# board.net
KiCad netlist of a schematic drawn in EAGLE
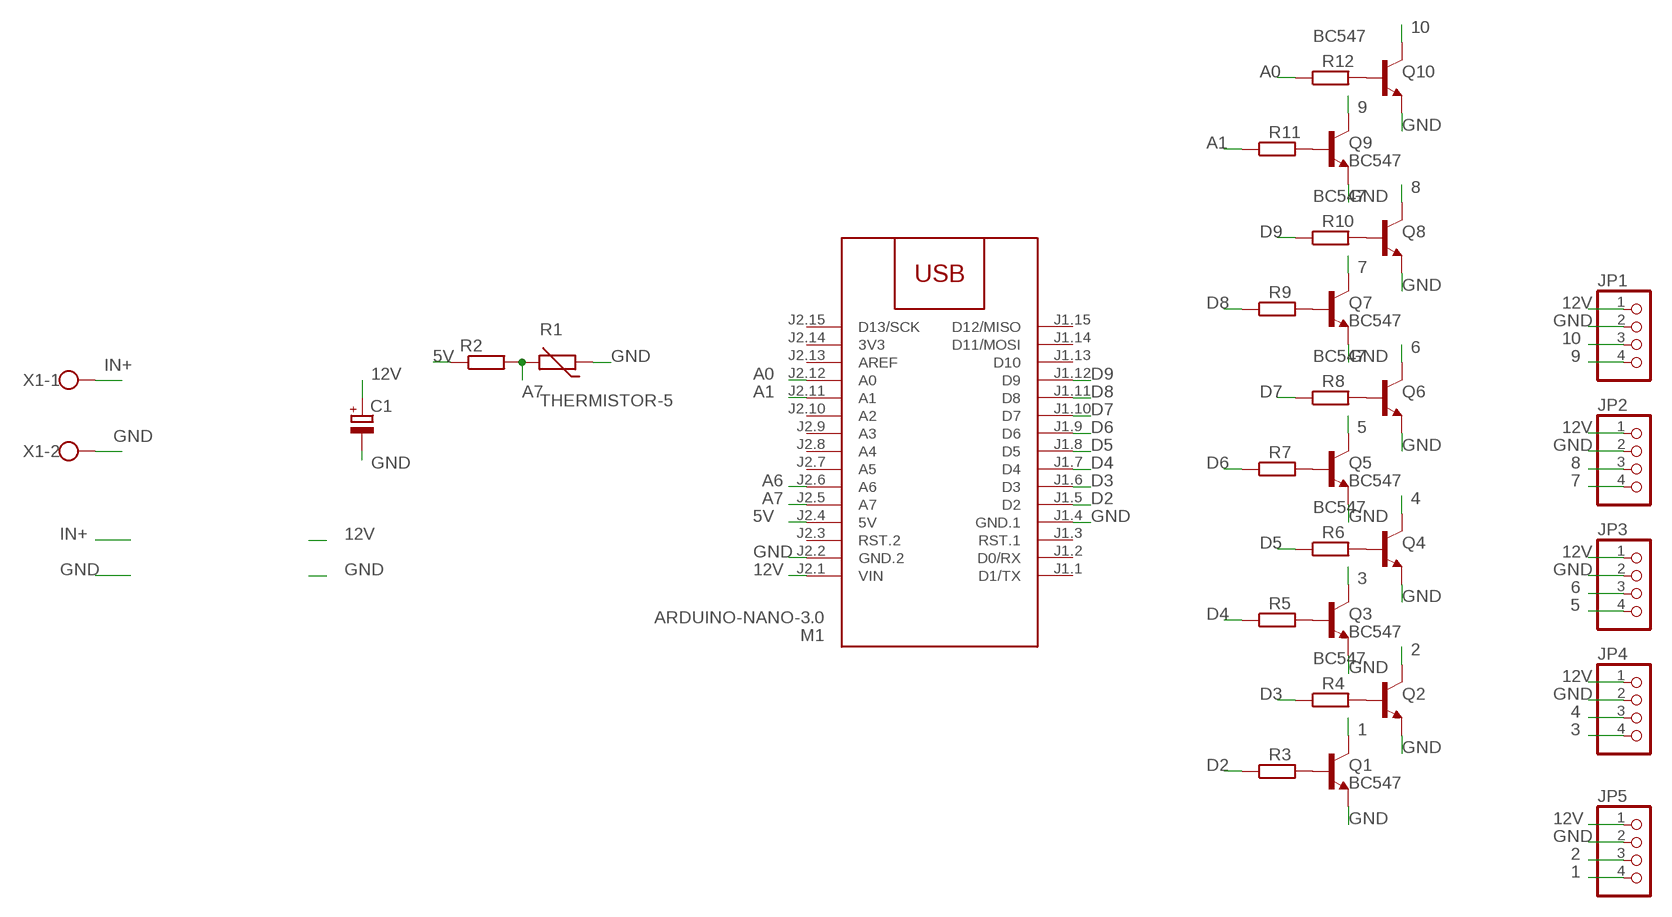
[diagram p0: schematic, sheet 1]

(export (version "E")
  (design (tool "Eeschema 10.0.6"))
  (components
    (comp (ref "C1")
      (value "CPOL-EUB45181A")
      (footprint "eagle-import:B45181A")
      (libsource (lib "eagle-import") (part "CPOL-EUB45181A"))
    )
    (comp (ref "JP1")
      (value "PINHD-1X4")
      (footprint "eagle-import:1X04")
      (libsource (lib "eagle-import") (part "PINHD-1X4"))
    )
    (comp (ref "JP2")
      (value "PINHD-1X4")
      (footprint "eagle-import:1X04")
      (libsource (lib "eagle-import") (part "PINHD-1X4"))
    )
    (comp (ref "JP3")
      (value "PINHD-1X4")
      (footprint "eagle-import:1X04")
      (libsource (lib "eagle-import") (part "PINHD-1X4"))
    )
    (comp (ref "JP4")
      (value "PINHD-1X4")
      (footprint "eagle-import:1X04")
      (libsource (lib "eagle-import") (part "PINHD-1X4"))
    )
    (comp (ref "JP5")
      (value "PINHD-1X4")
      (footprint "eagle-import:1X04")
      (libsource (lib "eagle-import") (part "PINHD-1X4"))
    )
    (comp (ref "M1")
      (value "ARDUINO-NANO-3.0")
      (footprint "eagle-import:ARDUINO-NANO-3.0")
      (libsource (lib "eagle-import") (part "ARDUINO-NANO-3.0"))
    )
    (comp (ref "Q1")
      (value "BC547")
      (footprint "eagle-import:TO92")
      (libsource (lib "eagle-import") (part "BC547"))
    )
    (comp (ref "Q2")
      (value "BC547")
      (footprint "eagle-import:TO92")
      (libsource (lib "eagle-import") (part "BC547"))
    )
    (comp (ref "Q3")
      (value "BC547")
      (footprint "eagle-import:TO92")
      (libsource (lib "eagle-import") (part "BC547"))
    )
    (comp (ref "Q4")
      (value "BC547")
      (footprint "eagle-import:TO92")
      (libsource (lib "eagle-import") (part "BC547"))
    )
    (comp (ref "Q5")
      (value "BC547")
      (footprint "eagle-import:TO92")
      (libsource (lib "eagle-import") (part "BC547"))
    )
    (comp (ref "Q6")
      (value "BC547")
      (footprint "eagle-import:TO92")
      (libsource (lib "eagle-import") (part "BC547"))
    )
    (comp (ref "Q7")
      (value "BC547")
      (footprint "eagle-import:TO92")
      (libsource (lib "eagle-import") (part "BC547"))
    )
    (comp (ref "Q8")
      (value "BC547")
      (footprint "eagle-import:TO92")
      (libsource (lib "eagle-import") (part "BC547"))
    )
    (comp (ref "Q9")
      (value "BC547")
      (footprint "eagle-import:TO92")
      (libsource (lib "eagle-import") (part "BC547"))
    )
    (comp (ref "Q10")
      (value "BC547")
      (footprint "eagle-import:TO92")
      (libsource (lib "eagle-import") (part "BC547"))
    )
    (comp (ref "R1")
      (value "THERMISTOR-5")
      (footprint "eagle-import:R-5")
      (libsource (lib "eagle-import") (part "THERMISTOR-5"))
    )
    (comp (ref "R2")
      (value "R-EU_0207/10")
      (footprint "eagle-import:0207_10")
      (libsource (lib "eagle-import") (part "R-EU_0207/10"))
    )
    (comp (ref "R3")
      (value "R-EU_0207/10")
      (footprint "eagle-import:0207_10")
      (libsource (lib "eagle-import") (part "R-EU_0207/10"))
    )
    (comp (ref "R4")
      (value "R-EU_0207/10")
      (footprint "eagle-import:0207_10")
      (libsource (lib "eagle-import") (part "R-EU_0207/10"))
    )
    (comp (ref "R5")
      (value "R-EU_0207/10")
      (footprint "eagle-import:0207_10")
      (libsource (lib "eagle-import") (part "R-EU_0207/10"))
    )
    (comp (ref "R6")
      (value "R-EU_0207/10")
      (footprint "eagle-import:0207_10")
      (libsource (lib "eagle-import") (part "R-EU_0207/10"))
    )
    (comp (ref "R7")
      (value "R-EU_0207/10")
      (footprint "eagle-import:0207_10")
      (libsource (lib "eagle-import") (part "R-EU_0207/10"))
    )
    (comp (ref "R8")
      (value "R-EU_0207/10")
      (footprint "eagle-import:0207_10")
      (libsource (lib "eagle-import") (part "R-EU_0207/10"))
    )
    (comp (ref "R9")
      (value "R-EU_0207/10")
      (footprint "eagle-import:0207_10")
      (libsource (lib "eagle-import") (part "R-EU_0207/10"))
    )
    (comp (ref "R10")
      (value "R-EU_0207/10")
      (footprint "eagle-import:0207_10")
      (libsource (lib "eagle-import") (part "R-EU_0207/10"))
    )
    (comp (ref "R11")
      (value "R-EU_0207/10")
      (footprint "eagle-import:0207_10")
      (libsource (lib "eagle-import") (part "R-EU_0207/10"))
    )
    (comp (ref "R12")
      (value "R-EU_0207/10")
      (footprint "eagle-import:0207_10")
      (libsource (lib "eagle-import") (part "R-EU_0207/10"))
    )
    (comp (ref "X1")
      (value "W237-102")
      (footprint "eagle-import:W237-102")
      (fields (field (name "MPN") "237-102"))
      (libsource (lib "eagle-import") (part "W237-102"))
    )
  )
  (nets
    (net (code "1") (name "/1") (class "Default")
      (node (ref "JP5") (pin "4") (pinfunction "4_4") (pintype "passive"))
      (node (ref "Q1") (pin "3") (pinfunction "C_3") (pintype "passive"))
    )
    (net (code "2") (name "/2") (class "Default")
      (node (ref "JP5") (pin "3") (pinfunction "3_3") (pintype "passive"))
      (node (ref "Q2") (pin "3") (pinfunction "C_3") (pintype "passive"))
    )
    (net (code "3") (name "/3") (class "Default")
      (node (ref "JP4") (pin "4") (pinfunction "4_4") (pintype "passive"))
      (node (ref "Q3") (pin "3") (pinfunction "C_3") (pintype "passive"))
    )
    (net (code "4") (name "/3V3") (class "Default")
      (node (ref "M1") (pin "J2.14") (pinfunction "3V3_J2.14") (pintype "power_in"))
    )
    (net (code "5") (name "/4") (class "Default")
      (node (ref "JP4") (pin "3") (pinfunction "3_3") (pintype "passive"))
      (node (ref "Q4") (pin "3") (pinfunction "C_3") (pintype "passive"))
    )
    (net (code "6") (name "/5") (class "Default")
      (node (ref "JP3") (pin "4") (pinfunction "4_4") (pintype "passive"))
      (node (ref "Q5") (pin "3") (pinfunction "C_3") (pintype "passive"))
    )
    (net (code "7") (name "/5V") (class "Default")
      (node (ref "M1") (pin "J2.4") (pinfunction "5V_J2.4") (pintype "power_in"))
      (node (ref "R2") (pin "1") (pinfunction "1_1") (pintype "passive"))
    )
    (net (code "8") (name "/6") (class "Default")
      (node (ref "JP3") (pin "3") (pinfunction "3_3") (pintype "passive"))
      (node (ref "Q6") (pin "3") (pinfunction "C_3") (pintype "passive"))
    )
    (net (code "9") (name "/7") (class "Default")
      (node (ref "JP2") (pin "4") (pinfunction "4_4") (pintype "passive"))
      (node (ref "Q7") (pin "3") (pinfunction "C_3") (pintype "passive"))
    )
    (net (code "10") (name "/8") (class "Default")
      (node (ref "JP2") (pin "3") (pinfunction "3_3") (pintype "passive"))
      (node (ref "Q8") (pin "3") (pinfunction "C_3") (pintype "passive"))
    )
    (net (code "11") (name "/9") (class "Default")
      (node (ref "JP1") (pin "4") (pinfunction "4_4") (pintype "passive"))
      (node (ref "Q9") (pin "3") (pinfunction "C_3") (pintype "passive"))
    )
    (net (code "12") (name "/10") (class "Default")
      (node (ref "JP1") (pin "3") (pinfunction "3_3") (pintype "passive"))
      (node (ref "Q10") (pin "3") (pinfunction "C_3") (pintype "passive"))
    )
    (net (code "13") (name "/12V") (class "Default")
      (node (ref "C1") (pin "+") (pinfunction "+_+") (pintype "passive"))
      (node (ref "JP1") (pin "1") (pinfunction "1_1") (pintype "passive"))
      (node (ref "JP2") (pin "1") (pinfunction "1_1") (pintype "passive"))
      (node (ref "JP3") (pin "1") (pinfunction "1_1") (pintype "passive"))
      (node (ref "JP4") (pin "1") (pinfunction "1_1") (pintype "passive"))
      (node (ref "JP5") (pin "1") (pinfunction "1_1") (pintype "passive"))
      (node (ref "M1") (pin "J2.1") (pinfunction "VIN_J2.1") (pintype "power_in"))
    )
    (net (code "14") (name "/A0") (class "Default")
      (node (ref "M1") (pin "J2.12") (pinfunction "A0_J2.12") (pintype "bidirectional"))
      (node (ref "R12") (pin "1") (pinfunction "1_1") (pintype "passive"))
    )
    (net (code "15") (name "/A1") (class "Default")
      (node (ref "M1") (pin "J2.11") (pinfunction "A1_J2.11") (pintype "bidirectional"))
      (node (ref "R11") (pin "1") (pinfunction "1_1") (pintype "passive"))
    )
    (net (code "16") (name "/A6") (class "Default")
      (node (ref "M1") (pin "J2.6") (pinfunction "A6_J2.6") (pintype "bidirectional"))
    )
    (net (code "17") (name "/A7") (class "Default")
      (node (ref "M1") (pin "J2.5") (pinfunction "A7_J2.5") (pintype "bidirectional"))
      (node (ref "R1") (pin "2") (pinfunction "2_2") (pintype "passive"))
      (node (ref "R2") (pin "2") (pinfunction "2_2") (pintype "passive"))
    )
    (net (code "18") (name "/D2") (class "Default")
      (node (ref "M1") (pin "J1.5") (pinfunction "D2_J1.5") (pintype "bidirectional"))
      (node (ref "R3") (pin "1") (pinfunction "1_1") (pintype "passive"))
    )
    (net (code "19") (name "/D3") (class "Default")
      (node (ref "M1") (pin "J1.6") (pinfunction "D3_J1.6") (pintype "bidirectional"))
      (node (ref "R4") (pin "1") (pinfunction "1_1") (pintype "passive"))
    )
    (net (code "20") (name "/D4") (class "Default")
      (node (ref "M1") (pin "J1.7") (pinfunction "D4_J1.7") (pintype "bidirectional"))
      (node (ref "R5") (pin "1") (pinfunction "1_1") (pintype "passive"))
    )
    (net (code "21") (name "/D5") (class "Default")
      (node (ref "M1") (pin "J1.8") (pinfunction "D5_J1.8") (pintype "bidirectional"))
      (node (ref "R6") (pin "1") (pinfunction "1_1") (pintype "passive"))
    )
    (net (code "22") (name "/D6") (class "Default")
      (node (ref "M1") (pin "J1.9") (pinfunction "D6_J1.9") (pintype "bidirectional"))
      (node (ref "R7") (pin "1") (pinfunction "1_1") (pintype "passive"))
    )
    (net (code "23") (name "/D7") (class "Default")
      (node (ref "M1") (pin "J1.10") (pinfunction "D7_J1.10") (pintype "bidirectional"))
      (node (ref "R8") (pin "1") (pinfunction "1_1") (pintype "passive"))
    )
    (net (code "24") (name "/D8") (class "Default")
      (node (ref "M1") (pin "J1.11") (pinfunction "D8_J1.11") (pintype "bidirectional"))
      (node (ref "R9") (pin "1") (pinfunction "1_1") (pintype "passive"))
    )
    (net (code "25") (name "/D9") (class "Default")
      (node (ref "M1") (pin "J1.12") (pinfunction "D9_J1.12") (pintype "bidirectional"))
      (node (ref "R10") (pin "1") (pinfunction "1_1") (pintype "passive"))
    )
    (net (code "26") (name "/GND") (class "Default")
      (node (ref "C1") (pin "-") (pinfunction "-_-") (pintype "passive"))
      (node (ref "JP1") (pin "2") (pinfunction "2_2") (pintype "passive"))
      (node (ref "JP2") (pin "2") (pinfunction "2_2") (pintype "passive"))
      (node (ref "JP3") (pin "2") (pinfunction "2_2") (pintype "passive"))
      (node (ref "JP4") (pin "2") (pinfunction "2_2") (pintype "passive"))
      (node (ref "JP5") (pin "2") (pinfunction "2_2") (pintype "passive"))
      (node (ref "M1") (pin "J1.4") (pinfunction "GND.1_J1.4") (pintype "power_in"))
      (node (ref "M1") (pin "J2.2") (pinfunction "GND.2_J2.2") (pintype "power_in"))
      (node (ref "Q1") (pin "1") (pinfunction "E_1") (pintype "passive"))
      (node (ref "Q10") (pin "1") (pinfunction "E_1") (pintype "passive"))
      (node (ref "Q2") (pin "1") (pinfunction "E_1") (pintype "passive"))
      (node (ref "Q3") (pin "1") (pinfunction "E_1") (pintype "passive"))
      (node (ref "Q4") (pin "1") (pinfunction "E_1") (pintype "passive"))
      (node (ref "Q5") (pin "1") (pinfunction "E_1") (pintype "passive"))
      (node (ref "Q6") (pin "1") (pinfunction "E_1") (pintype "passive"))
      (node (ref "Q7") (pin "1") (pinfunction "E_1") (pintype "passive"))
      (node (ref "Q8") (pin "1") (pinfunction "E_1") (pintype "passive"))
      (node (ref "Q9") (pin "1") (pinfunction "E_1") (pintype "passive"))
      (node (ref "R1") (pin "1") (pinfunction "1_1") (pintype "passive"))
      (node (ref "X1") (pin "2") (pinfunction "KL_2") (pintype "passive"))
    )
    (net (code "27") (name "/IN+") (class "Default")
      (node (ref "X1") (pin "1") (pinfunction "KL_1") (pintype "passive"))
    )
    (net (code "28") (name "Net-(Q1-B)") (class "Default")
      (node (ref "Q1") (pin "2") (pinfunction "B_2") (pintype "passive"))
      (node (ref "R3") (pin "2") (pinfunction "2_2") (pintype "passive"))
    )
    (net (code "29") (name "Net-(Q2-B)") (class "Default")
      (node (ref "Q2") (pin "2") (pinfunction "B_2") (pintype "passive"))
      (node (ref "R4") (pin "2") (pinfunction "2_2") (pintype "passive"))
    )
    (net (code "30") (name "Net-(Q3-B)") (class "Default")
      (node (ref "Q3") (pin "2") (pinfunction "B_2") (pintype "passive"))
      (node (ref "R5") (pin "2") (pinfunction "2_2") (pintype "passive"))
    )
    (net (code "31") (name "Net-(Q4-B)") (class "Default")
      (node (ref "Q4") (pin "2") (pinfunction "B_2") (pintype "passive"))
      (node (ref "R6") (pin "2") (pinfunction "2_2") (pintype "passive"))
    )
    (net (code "32") (name "Net-(Q5-B)") (class "Default")
      (node (ref "Q5") (pin "2") (pinfunction "B_2") (pintype "passive"))
      (node (ref "R7") (pin "2") (pinfunction "2_2") (pintype "passive"))
    )
    (net (code "33") (name "Net-(Q6-B)") (class "Default")
      (node (ref "Q6") (pin "2") (pinfunction "B_2") (pintype "passive"))
      (node (ref "R8") (pin "2") (pinfunction "2_2") (pintype "passive"))
    )
    (net (code "34") (name "Net-(Q7-B)") (class "Default")
      (node (ref "Q7") (pin "2") (pinfunction "B_2") (pintype "passive"))
      (node (ref "R9") (pin "2") (pinfunction "2_2") (pintype "passive"))
    )
    (net (code "35") (name "Net-(Q8-B)") (class "Default")
      (node (ref "Q8") (pin "2") (pinfunction "B_2") (pintype "passive"))
      (node (ref "R10") (pin "2") (pinfunction "2_2") (pintype "passive"))
    )
    (net (code "36") (name "Net-(Q9-B)") (class "Default")
      (node (ref "Q9") (pin "2") (pinfunction "B_2") (pintype "passive"))
      (node (ref "R11") (pin "2") (pinfunction "2_2") (pintype "passive"))
    )
    (net (code "37") (name "Net-(Q10-B)") (class "Default")
      (node (ref "Q10") (pin "2") (pinfunction "B_2") (pintype "passive"))
      (node (ref "R12") (pin "2") (pinfunction "2_2") (pintype "passive"))
    )
    (net (code "38") (name "unconnected-(M1-A2-PadJ2.10)") (class "Default")
      (node (ref "M1") (pin "J2.10") (pinfunction "A2_J2.10") (pintype "bidirectional"))
    )
    (net (code "39") (name "unconnected-(M1-A3-PadJ2.9)") (class "Default")
      (node (ref "M1") (pin "J2.9") (pinfunction "A3_J2.9") (pintype "bidirectional"))
    )
    (net (code "40") (name "unconnected-(M1-A4-PadJ2.8)") (class "Default")
      (node (ref "M1") (pin "J2.8") (pinfunction "A4_J2.8") (pintype "bidirectional"))
    )
    (net (code "41") (name "unconnected-(M1-A5-PadJ2.7)") (class "Default")
      (node (ref "M1") (pin "J2.7") (pinfunction "A5_J2.7") (pintype "bidirectional"))
    )
    (net (code "42") (name "unconnected-(M1-AREF-PadJ2.13)") (class "Default")
      (node (ref "M1") (pin "J2.13") (pinfunction "AREF_J2.13") (pintype "bidirectional"))
    )
    (net (code "43") (name "unconnected-(M1-D0{slash}RX-PadJ1.2)") (class "Default")
      (node (ref "M1") (pin "J1.2") (pinfunction "D0/RX_J1.2") (pintype "bidirectional"))
    )
    (net (code "44") (name "unconnected-(M1-D1{slash}TX-PadJ1.1)") (class "Default")
      (node (ref "M1") (pin "J1.1") (pinfunction "D1/TX_J1.1") (pintype "bidirectional"))
    )
    (net (code "45") (name "unconnected-(M1-D10-PadJ1.13)") (class "Default")
      (node (ref "M1") (pin "J1.13") (pinfunction "D10_J1.13") (pintype "bidirectional"))
    )
    (net (code "46") (name "unconnected-(M1-D11{slash}MOSI-PadJ1.14)") (class "Default")
      (node (ref "M1") (pin "J1.14") (pinfunction "D11/MOSI_J1.14") (pintype "bidirectional"))
    )
    (net (code "47") (name "unconnected-(M1-D12{slash}MISO-PadJ1.15)") (class "Default")
      (node (ref "M1") (pin "J1.15") (pinfunction "D12/MISO_J1.15") (pintype "bidirectional"))
    )
    (net (code "48") (name "unconnected-(M1-D13{slash}SCK-PadJ2.15)") (class "Default")
      (node (ref "M1") (pin "J2.15") (pinfunction "D13/SCK_J2.15") (pintype "bidirectional"))
    )
    (net (code "49") (name "unconnected-(M1-RST.1-PadJ1.3)") (class "Default")
      (node (ref "M1") (pin "J1.3") (pinfunction "RST.1_J1.3") (pintype "bidirectional"))
    )
    (net (code "50") (name "unconnected-(M1-RST.2-PadJ2.3)") (class "Default")
      (node (ref "M1") (pin "J2.3") (pinfunction "RST.2_J2.3") (pintype "bidirectional"))
    )
  )
)
